# PCIe-M2.net
KiCad netlist of a schematic drawn in Altium Designer
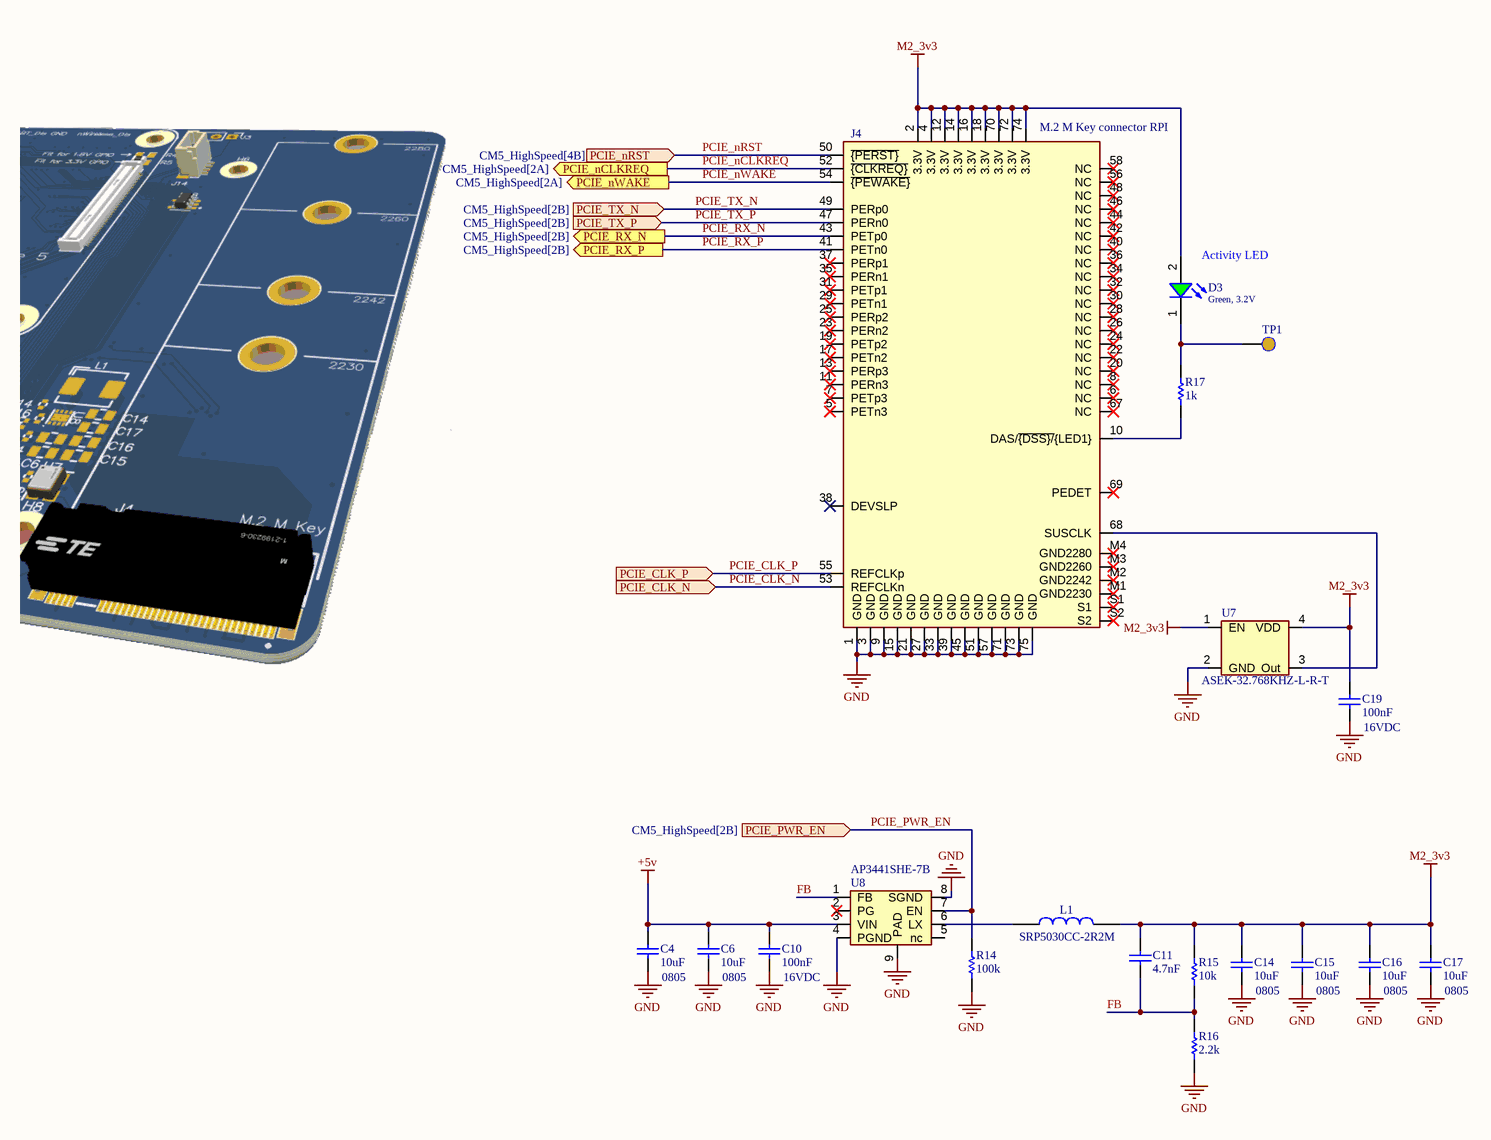
[diagram p0: PCIe-M2.SchDoc]

(export (version "E")
  (design (tool "Eeschema 10.0.6"))
  (components
    (comp (ref "C4")
      (value "10uF")
      (footprint "WCAP-CSGP_0805_H=1.25mm")
      (description "WCAP-CSGP Multilayer Ceramic Chip Capacitor, General Purpose, size 0805, X5R, 10uF, 16V")
      (fields
        (field (name "MANUFACTURER") "Wurth Elektronik")
        (field (name "MANUFACTURER PART NUMBER") "885012107014")
        (field (name "SIZE") "0805")
      )
      (libsource (lib "Q-WAVE SYSTEMS CO") (part "Symbol"))
    )
    (comp (ref "C6")
      (value "10uF")
      (footprint "WCAP-CSGP_0805_H=1.25mm")
      (description "WCAP-CSGP Multilayer Ceramic Chip Capacitor, General Purpose, size 0805, X5R, 10uF, 16V")
      (fields
        (field (name "MANUFACTURER") "Wurth Elektronik")
        (field (name "MANUFACTURER PART NUMBER") "885012107014")
        (field (name "SIZE") "0805")
      )
      (libsource (lib "Q-WAVE SYSTEMS CO") (part "Symbol"))
    )
    (comp (ref "C10")
      (value "100nF")
      (footprint "WCAP-CSGP_0402_H=0.5mm")
      (description "WCAP-CSGP Multilayer Ceramic Chip Capacitor, General Purpose, size 0402, X5R, 100nF, 16V")
      (fields
        (field (name "MANUFACTURER PART NUMBER") "885012105016")
        (field (name "MANUFACTURER") "Wurth Elektronik")
        (field (name "RATED VOLTAGE") "16VDC")
      )
      (libsource (lib "Q-WAVE SYSTEMS CO") (part "Symbol"))
    )
    (comp (ref "C11")
      (value "4.7nF")
      (footprint "WCAP-CSGP_0402_H=0.5mm")
      (description "WCAP-CSGP Multilayer Ceramic Chip Capacitor, General Purpose, size 0402, X7R, 4.7nF, 16V")
      (fields
        (field (name "MANUFACTURER") "Wurth Elektronik")
        (field (name "MANUFACTURER PART NUMBER") "885012205029")
      )
      (libsource (lib "Q-WAVE SYSTEMS CO") (part "Symbol"))
    )
    (comp (ref "C14")
      (value "10uF")
      (footprint "WCAP-CSGP_0805_H=1.25mm")
      (description "WCAP-CSGP Multilayer Ceramic Chip Capacitor, General Purpose, size 0805, X5R, 10uF, 16V")
      (fields
        (field (name "MANUFACTURER") "Wurth Elektronik")
        (field (name "MANUFACTURER PART NUMBER") "885012107014")
        (field (name "SIZE") "0805")
      )
      (libsource (lib "Q-WAVE SYSTEMS CO") (part "Symbol"))
    )
    (comp (ref "C15")
      (value "10uF")
      (footprint "WCAP-CSGP_0805_H=1.25mm")
      (description "WCAP-CSGP Multilayer Ceramic Chip Capacitor, General Purpose, size 0805, X5R, 10uF, 16V")
      (fields
        (field (name "MANUFACTURER") "Wurth Elektronik")
        (field (name "MANUFACTURER PART NUMBER") "885012107014")
        (field (name "SIZE") "0805")
      )
      (libsource (lib "Q-WAVE SYSTEMS CO") (part "Symbol"))
    )
    (comp (ref "C16")
      (value "10uF")
      (footprint "WCAP-CSGP_0805_H=1.25mm")
      (description "WCAP-CSGP Multilayer Ceramic Chip Capacitor, General Purpose, size 0805, X5R, 10uF, 16V")
      (fields
        (field (name "MANUFACTURER") "Wurth Elektronik")
        (field (name "MANUFACTURER PART NUMBER") "885012107014")
        (field (name "SIZE") "0805")
      )
      (libsource (lib "Q-WAVE SYSTEMS CO") (part "Symbol"))
    )
    (comp (ref "C17")
      (value "10uF")
      (footprint "WCAP-CSGP_0805_H=1.25mm")
      (description "WCAP-CSGP Multilayer Ceramic Chip Capacitor, General Purpose, size 0805, X5R, 10uF, 16V")
      (fields
        (field (name "MANUFACTURER") "Wurth Elektronik")
        (field (name "MANUFACTURER PART NUMBER") "885012107014")
        (field (name "SIZE") "0805")
      )
      (libsource (lib "Q-WAVE SYSTEMS CO") (part "Symbol"))
    )
    (comp (ref "C19")
      (value "100nF")
      (footprint "WCAP-CSGP_0402_H=0.5mm")
      (description "WCAP-CSGP Multilayer Ceramic Chip Capacitor, General Purpose, size 0402, X5R, 100nF, 16V")
      (fields
        (field (name "MANUFACTURER PART NUMBER") "885012105016")
        (field (name "MANUFACTURER") "Wurth Elektronik")
        (field (name "RATED VOLTAGE") "16VDC")
      )
      (libsource (lib "Q-WAVE SYSTEMS CO") (part "Symbol"))
    )
    (comp (ref "D3")
      (value "Green, 3.2V")
      (footprint "WL-SMCW_0603_H=0.7mm_Green")
      (description "WL-SMCW SMT Mono-color Chip LED Waterclear, size 0603, Green, 3.2V, 140deg")
      (fields (field (name "PART NUMBER") "150060GS75000") (field (name "PUBLISHER") "Wurth Elektronik"))
      (libsource (lib "") (part "Symbol_1"))
    )
    (comp (ref "J4")
      (value "M.2 M Key connector RPI")
      (footprint "M.2 M Key connector RPI")
      (description "M.2 NGFF M-KEY H4.2mm Conn Card Edge SKT 67 POS 0.5mm Solder RA SMD T/R")
      (libsource (lib "Q-WAVE SYSTEMS CO") (part "M.2 M Key connector RPI"))
    )
    (comp (ref "L1")
      (value "SRP5030CC-2R2M")
      (footprint "SRP5030CC-2R2M")
      (libsource (lib "Q-WAVE SYSTEMS CO") (part "SRP5030CC-2R2M"))
    )
    (comp (ref "R14")
      (value "100k")
      (footprint "SMD-0402-RES")
      (description "RES SMD 100K OHM 1% 1/10W 0402")
      (fields
        (field (name "TOLERANCE") "±1%")
        (field (name "MANUFACTURER") "Panasonic Electronic Components")
      )
      (libsource (lib "Q-WAVE SYSTEMS CO") (part "resistor"))
    )
    (comp (ref "R15")
      (value "10k")
      (footprint "SMD-0402-RES")
      (description "RES SMD 10K OHM 1% 1/10W 0402")
      (fields
        (field (name "MANUFACTURER") "Panasonic Electronic Components")
        (field (name "DIGI-KEY PART NUMBER") "P10.0KLCT-ND")
      )
      (libsource (lib "Q-WAVE SYSTEMS CO") (part "resistor"))
    )
    (comp (ref "R16")
      (value "2.2k")
      (footprint "SMD-0402-RES")
      (description "RES SMD 2.2K OHM 1% 1/10W 0402")
      (fields (field (name "TOLERANCE") "±1%") (field (name "PART NUMBER") "ERJ-2RKF2201X"))
      (libsource (lib "Q-WAVE SYSTEMS CO") (part "resistor"))
    )
    (comp (ref "R17")
      (value "1k")
      (footprint "SMD-0402-RES")
      (description "RES SMD 1K OHM 1% 1/10W 0402")
      (fields
        (field (name "MANUFACTURER") "Panasonic Electronic Components")
        (field (name "TOLERANCE") "±1%")
      )
      (libsource (lib "Q-WAVE SYSTEMS CO") (part "resistor"))
    )
    (comp (ref "TP1")
      (value "TEST_POINT 1")
      (footprint "TEST_POINT 1")
      (description "Test Point SMT PAD")
      (libsource (lib "Q-WAVE SYSTEMS CO") (part "TEST_POINT 1"))
    )
    (comp (ref "U7")
      (value "ASEK-32.768KHZ-L-R-T")
      (footprint "ASEK-32.768KHZ-L-R-T")
      (description "Oscillator XO 0.032768MHz ±25ppm 15pF 60% 3.3V 4-Pin SMD T/R")
      (libsource (lib "Q-WAVE SYSTEMS CO") (part "ASEK-32.768KHZ-L-R-T"))
    )
    (comp (ref "U8")
      (value "AP3441SHE-7B")
      (footprint "AP3441SHE-7B")
      (description "Dc/dc Conv, Buck, 1Mhz, -40 To 85Deg C Rohs Compliant: Yes")
      (libsource (lib "Q-WAVE SYSTEMS CO") (part "AP3441SHE-7B"))
    )
  )
  (nets
    (net (code "1") (name "+5v") (class "Default")
      (node (ref "C10") (pin "2") (pinfunction "2_2") (pintype "passive"))
      (node (ref "C4") (pin "2") (pinfunction "2_2") (pintype "passive"))
      (node (ref "C6") (pin "2") (pinfunction "2_2") (pintype "passive"))
      (node (ref "U8") (pin "3") (pinfunction "VIN_3") (pintype "passive"))
    )
    (net (code "2") (name "/FB") (class "Default")
      (node (ref "C11") (pin "1") (pinfunction "1_1") (pintype "passive"))
      (node (ref "R15") (pin "1") (pinfunction "1_1") (pintype "passive"))
      (node (ref "R16") (pin "2") (pinfunction "2_2") (pintype "passive"))
      (node (ref "U8") (pin "1") (pinfunction "FB_1") (pintype "passive"))
    )
    (net (code "3") (name "/PCIE_CLK_N") (class "Default")
      (node (ref "J4") (pin "53") (pinfunction "REFCLKn_53") (pintype "passive"))
    )
    (net (code "4") (name "/PCIE_CLK_P") (class "Default")
      (node (ref "J4") (pin "55") (pinfunction "REFCLKp_55") (pintype "passive"))
    )
    (net (code "5") (name "/PCIE_PWR_EN") (class "Default")
      (node (ref "R14") (pin "2") (pinfunction "2_2") (pintype "passive"))
      (node (ref "U8") (pin "7") (pinfunction "EN_7") (pintype "passive"))
    )
    (net (code "6") (name "/PCIE_RX_N") (class "Default")
      (node (ref "J4") (pin "43") (pinfunction "PETp0_43") (pintype "passive"))
    )
    (net (code "7") (name "/PCIE_RX_P") (class "Default")
      (node (ref "J4") (pin "41") (pinfunction "PETn0_41") (pintype "passive"))
    )
    (net (code "8") (name "/PCIE_TX_N") (class "Default")
      (node (ref "J4") (pin "49") (pinfunction "PERp0_49") (pintype "passive"))
    )
    (net (code "9") (name "/PCIE_TX_P") (class "Default")
      (node (ref "J4") (pin "47") (pinfunction "PERn0_47") (pintype "passive"))
    )
    (net (code "10") (name "/PCIE_nCLKREQ") (class "Default")
      (node (ref "J4") (pin "52") (pinfunction "~{{CLKREQ}}_52") (pintype "passive"))
    )
    (net (code "11") (name "/PCIE_nRST") (class "Default")
      (node (ref "J4") (pin "50") (pinfunction "~{{PERST}}_50") (pintype "passive"))
    )
    (net (code "12") (name "/PCIE_nWAKE") (class "Default")
      (node (ref "J4") (pin "54") (pinfunction "~{{PEWAKE}}_54") (pintype "passive"))
    )
    (net (code "13") (name "GND") (class "Default")
      (node (ref "C10") (pin "1") (pinfunction "1_1") (pintype "passive"))
      (node (ref "C14") (pin "1") (pinfunction "1_1") (pintype "passive"))
      (node (ref "C15") (pin "1") (pinfunction "1_1") (pintype "passive"))
      (node (ref "C16") (pin "1") (pinfunction "1_1") (pintype "passive"))
      (node (ref "C17") (pin "1") (pinfunction "1_1") (pintype "passive"))
      (node (ref "C19") (pin "1") (pinfunction "1_1") (pintype "passive"))
      (node (ref "C4") (pin "1") (pinfunction "1_1") (pintype "passive"))
      (node (ref "C6") (pin "1") (pinfunction "1_1") (pintype "passive"))
      (node (ref "J4") (pin "1") (pinfunction "GND_1") (pintype "passive"))
      (node (ref "J4") (pin "15") (pinfunction "GND_15") (pintype "passive"))
      (node (ref "J4") (pin "21") (pinfunction "GND_21") (pintype "passive"))
      (node (ref "J4") (pin "27") (pinfunction "GND_27") (pintype "passive"))
      (node (ref "J4") (pin "3") (pinfunction "GND_3") (pintype "passive"))
      (node (ref "J4") (pin "33") (pinfunction "GND_33") (pintype "passive"))
      (node (ref "J4") (pin "39") (pinfunction "GND_39") (pintype "passive"))
      (node (ref "J4") (pin "45") (pinfunction "GND_45") (pintype "passive"))
      (node (ref "J4") (pin "51") (pinfunction "GND_51") (pintype "passive"))
      (node (ref "J4") (pin "57") (pinfunction "GND_57") (pintype "passive"))
      (node (ref "J4") (pin "71") (pinfunction "GND_71") (pintype "passive"))
      (node (ref "J4") (pin "73") (pinfunction "GND_73") (pintype "passive"))
      (node (ref "J4") (pin "75") (pinfunction "GND_75") (pintype "passive"))
      (node (ref "J4") (pin "9") (pinfunction "GND_9") (pintype "passive"))
      (node (ref "R14") (pin "1") (pinfunction "1_1") (pintype "passive"))
      (node (ref "R16") (pin "1") (pinfunction "1_1") (pintype "passive"))
      (node (ref "U7") (pin "2") (pinfunction "GND_2") (pintype "passive"))
      (node (ref "U8") (pin "4") (pinfunction "PGND_4") (pintype "passive"))
      (node (ref "U8") (pin "8") (pinfunction "SGND_8") (pintype "passive"))
      (node (ref "U8") (pin "9") (pinfunction "PAD_9") (pintype "passive"))
    )
    (net (code "14") (name "M2_3v3") (class "Default")
      (node (ref "C11") (pin "2") (pinfunction "2_2") (pintype "passive"))
      (node (ref "C14") (pin "2") (pinfunction "2_2") (pintype "passive"))
      (node (ref "C15") (pin "2") (pinfunction "2_2") (pintype "passive"))
      (node (ref "C16") (pin "2") (pinfunction "2_2") (pintype "passive"))
      (node (ref "C17") (pin "2") (pinfunction "2_2") (pintype "passive"))
      (node (ref "C19") (pin "2") (pinfunction "2_2") (pintype "passive"))
      (node (ref "D3") (pin "2") (pinfunction "A_2") (pintype "passive"))
      (node (ref "J4") (pin "12") (pinfunction "3.3V_12") (pintype "passive"))
      (node (ref "J4") (pin "14") (pinfunction "3.3V_14") (pintype "passive"))
      (node (ref "J4") (pin "16") (pinfunction "3.3V_16") (pintype "passive"))
      (node (ref "J4") (pin "18") (pinfunction "3.3V_18") (pintype "passive"))
      (node (ref "J4") (pin "2") (pinfunction "3.3V_2") (pintype "passive"))
      (node (ref "J4") (pin "4") (pinfunction "3.3V_4") (pintype "passive"))
      (node (ref "J4") (pin "70") (pinfunction "3.3V_70") (pintype "passive"))
      (node (ref "J4") (pin "72") (pinfunction "3.3V_72") (pintype "passive"))
      (node (ref "J4") (pin "74") (pinfunction "3.3V_74") (pintype "passive"))
      (node (ref "L1") (pin "2") (pinfunction "2_2") (pintype "passive"))
      (node (ref "R15") (pin "2") (pinfunction "2_2") (pintype "passive"))
      (node (ref "U7") (pin "1") (pinfunction "EN_1") (pintype "passive"))
      (node (ref "U7") (pin "4") (pinfunction "VDD_4") (pintype "passive"))
    )
    (net (code "15") (name "Net-(D3-K)") (class "Default")
      (node (ref "D3") (pin "1") (pinfunction "K_1") (pintype "passive"))
      (node (ref "R17") (pin "2") (pinfunction "2_2") (pintype "passive"))
      (node (ref "TP1") (pin "1") (pinfunction "1_1") (pintype "passive"))
    )
    (net (code "16") (name "Net-(J4-DAS{slash}~{{DSS}{slash}}{LED1})") (class "Default")
      (node (ref "J4") (pin "10") (pinfunction "DAS/~{{DSS}/}{LED1}_10") (pintype "passive"))
      (node (ref "R17") (pin "1") (pinfunction "1_1") (pintype "passive"))
    )
    (net (code "17") (name "Net-(J4-SUSCLK)") (class "Default")
      (node (ref "J4") (pin "68") (pinfunction "SUSCLK_68") (pintype "passive"))
      (node (ref "U7") (pin "3") (pinfunction "Out_3") (pintype "passive"))
    )
    (net (code "18") (name "Net-(U8-LX)") (class "Default")
      (node (ref "L1") (pin "1") (pinfunction "1_1") (pintype "passive"))
      (node (ref "U8") (pin "6") (pinfunction "LX_6") (pintype "passive"))
    )
    (net (code "19") (name "unconnected-(J4-DEVSLP-Pad38)") (class "Default")
      (node (ref "J4") (pin "38") (pinfunction "DEVSLP_38") (pintype "passive+no_connect"))
    )
    (net (code "20") (name "unconnected-(J4-GND2230-PadM1)") (class "Default")
      (node (ref "J4") (pin "M1") (pinfunction "GND2230_M1") (pintype "passive+no_connect"))
    )
    (net (code "21") (name "unconnected-(J4-GND2242-PadM2)") (class "Default")
      (node (ref "J4") (pin "M2") (pinfunction "GND2242_M2") (pintype "passive+no_connect"))
    )
    (net (code "22") (name "unconnected-(J4-GND2260-PadM3)") (class "Default")
      (node (ref "J4") (pin "M3") (pinfunction "GND2260_M3") (pintype "passive+no_connect"))
    )
    (net (code "23") (name "unconnected-(J4-GND2280-PadM4)") (class "Default")
      (node (ref "J4") (pin "M4") (pinfunction "GND2280_M4") (pintype "passive+no_connect"))
    )
    (net (code "24") (name "unconnected-(J4-NC-Pad6)") (class "Default")
      (node (ref "J4") (pin "6") (pinfunction "NC_6") (pintype "passive+no_connect"))
    )
    (net (code "25") (name "unconnected-(J4-NC-Pad8)") (class "Default")
      (node (ref "J4") (pin "8") (pinfunction "NC_8") (pintype "passive+no_connect"))
    )
    (net (code "26") (name "unconnected-(J4-NC-Pad20)") (class "Default")
      (node (ref "J4") (pin "20") (pinfunction "NC_20") (pintype "passive+no_connect"))
    )
    (net (code "27") (name "unconnected-(J4-NC-Pad22)") (class "Default")
      (node (ref "J4") (pin "22") (pinfunction "NC_22") (pintype "passive+no_connect"))
    )
    (net (code "28") (name "unconnected-(J4-NC-Pad24)") (class "Default")
      (node (ref "J4") (pin "24") (pinfunction "NC_24") (pintype "passive+no_connect"))
    )
    (net (code "29") (name "unconnected-(J4-NC-Pad26)") (class "Default")
      (node (ref "J4") (pin "26") (pinfunction "NC_26") (pintype "passive+no_connect"))
    )
    (net (code "30") (name "unconnected-(J4-NC-Pad28)") (class "Default")
      (node (ref "J4") (pin "28") (pinfunction "NC_28") (pintype "passive+no_connect"))
    )
    (net (code "31") (name "unconnected-(J4-NC-Pad30)") (class "Default")
      (node (ref "J4") (pin "30") (pinfunction "NC_30") (pintype "passive+no_connect"))
    )
    (net (code "32") (name "unconnected-(J4-NC-Pad32)") (class "Default")
      (node (ref "J4") (pin "32") (pinfunction "NC_32") (pintype "passive+no_connect"))
    )
    (net (code "33") (name "unconnected-(J4-NC-Pad34)") (class "Default")
      (node (ref "J4") (pin "34") (pinfunction "NC_34") (pintype "passive+no_connect"))
    )
    (net (code "34") (name "unconnected-(J4-NC-Pad36)") (class "Default")
      (node (ref "J4") (pin "36") (pinfunction "NC_36") (pintype "passive+no_connect"))
    )
    (net (code "35") (name "unconnected-(J4-NC-Pad40)") (class "Default")
      (node (ref "J4") (pin "40") (pinfunction "NC_40") (pintype "passive+no_connect"))
    )
    (net (code "36") (name "unconnected-(J4-NC-Pad42)") (class "Default")
      (node (ref "J4") (pin "42") (pinfunction "NC_42") (pintype "passive+no_connect"))
    )
    (net (code "37") (name "unconnected-(J4-NC-Pad44)") (class "Default")
      (node (ref "J4") (pin "44") (pinfunction "NC_44") (pintype "passive+no_connect"))
    )
    (net (code "38") (name "unconnected-(J4-NC-Pad46)") (class "Default")
      (node (ref "J4") (pin "46") (pinfunction "NC_46") (pintype "passive+no_connect"))
    )
    (net (code "39") (name "unconnected-(J4-NC-Pad48)") (class "Default")
      (node (ref "J4") (pin "48") (pinfunction "NC_48") (pintype "passive+no_connect"))
    )
    (net (code "40") (name "unconnected-(J4-NC-Pad56)") (class "Default")
      (node (ref "J4") (pin "56") (pinfunction "NC_56") (pintype "passive+no_connect"))
    )
    (net (code "41") (name "unconnected-(J4-NC-Pad58)") (class "Default")
      (node (ref "J4") (pin "58") (pinfunction "NC_58") (pintype "passive+no_connect"))
    )
    (net (code "42") (name "unconnected-(J4-NC-Pad67)") (class "Default")
      (node (ref "J4") (pin "67") (pinfunction "NC_67") (pintype "passive+no_connect"))
    )
    (net (code "43") (name "unconnected-(J4-PEDET-Pad69)") (class "Default")
      (node (ref "J4") (pin "69") (pinfunction "PEDET_69") (pintype "passive+no_connect"))
    )
    (net (code "44") (name "unconnected-(J4-PERn1-Pad35)") (class "Default")
      (node (ref "J4") (pin "35") (pinfunction "PERn1_35") (pintype "passive+no_connect"))
    )
    (net (code "45") (name "unconnected-(J4-PERn2-Pad23)") (class "Default")
      (node (ref "J4") (pin "23") (pinfunction "PERn2_23") (pintype "passive+no_connect"))
    )
    (net (code "46") (name "unconnected-(J4-PERn3-Pad11)") (class "Default")
      (node (ref "J4") (pin "11") (pinfunction "PERn3_11") (pintype "passive+no_connect"))
    )
    (net (code "47") (name "unconnected-(J4-PERp1-Pad37)") (class "Default")
      (node (ref "J4") (pin "37") (pinfunction "PERp1_37") (pintype "passive+no_connect"))
    )
    (net (code "48") (name "unconnected-(J4-PERp2-Pad25)") (class "Default")
      (node (ref "J4") (pin "25") (pinfunction "PERp2_25") (pintype "passive+no_connect"))
    )
    (net (code "49") (name "unconnected-(J4-PERp3-Pad13)") (class "Default")
      (node (ref "J4") (pin "13") (pinfunction "PERp3_13") (pintype "passive+no_connect"))
    )
    (net (code "50") (name "unconnected-(J4-PETn1-Pad29)") (class "Default")
      (node (ref "J4") (pin "29") (pinfunction "PETn1_29") (pintype "passive+no_connect"))
    )
    (net (code "51") (name "unconnected-(J4-PETn2-Pad17)") (class "Default")
      (node (ref "J4") (pin "17") (pinfunction "PETn2_17") (pintype "passive+no_connect"))
    )
    (net (code "52") (name "unconnected-(J4-PETn3-Pad5)") (class "Default")
      (node (ref "J4") (pin "5") (pinfunction "PETn3_5") (pintype "passive+no_connect"))
    )
    (net (code "53") (name "unconnected-(J4-PETp1-Pad31)") (class "Default")
      (node (ref "J4") (pin "31") (pinfunction "PETp1_31") (pintype "passive+no_connect"))
    )
    (net (code "54") (name "unconnected-(J4-PETp2-Pad19)") (class "Default")
      (node (ref "J4") (pin "19") (pinfunction "PETp2_19") (pintype "passive+no_connect"))
    )
    (net (code "55") (name "unconnected-(J4-PETp3-Pad7)") (class "Default")
      (node (ref "J4") (pin "7") (pinfunction "PETp3_7") (pintype "passive+no_connect"))
    )
    (net (code "56") (name "unconnected-(J4-PadS1)") (class "Default")
      (node (ref "J4") (pin "S1") (pinfunction "S1_S1") (pintype "passive+no_connect"))
    )
    (net (code "57") (name "unconnected-(J4-PadS2)") (class "Default")
      (node (ref "J4") (pin "S2") (pinfunction "S2_S2") (pintype "passive+no_connect"))
    )
    (net (code "58") (name "unconnected-(U8-PG-Pad2)") (class "Default")
      (node (ref "U8") (pin "2") (pinfunction "PG_2") (pintype "passive+no_connect"))
    )
    (net (code "59") (name "unconnected-(U8-nc-Pad5)") (class "Default")
      (node (ref "U8") (pin "5") (pinfunction "nc_5") (pintype "passive"))
    )
  )
)
